# plansza_do_teleturnieju.net
KiCad netlist of a schematic drawn in EAGLE
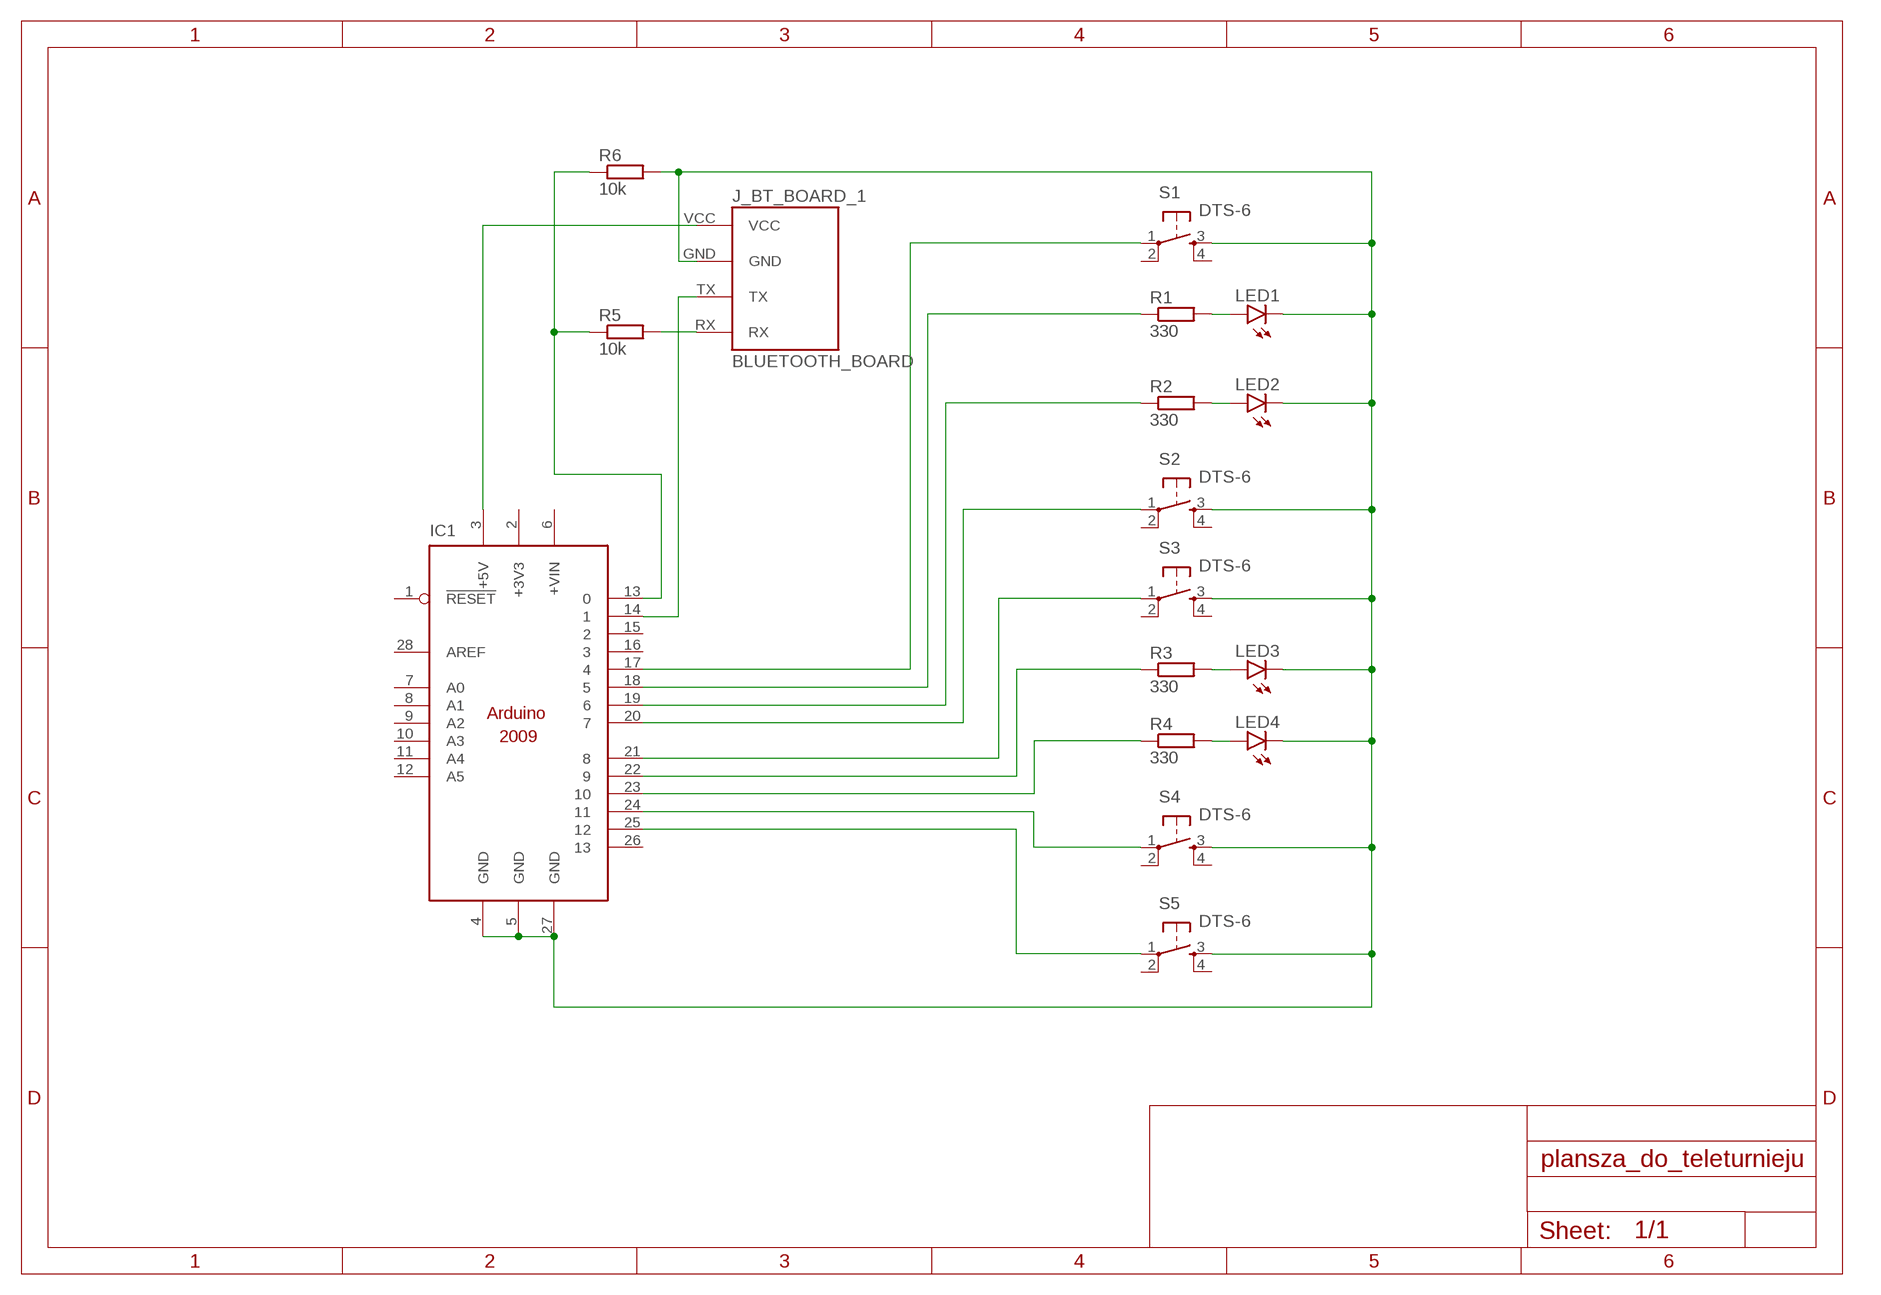
[diagram p0: schematic, sheet 1]

(export (version "E")
  (design (tool "Eeschema 10.0.6"))
  (components
    (comp (ref "IC1")
      (value "ARDUINO2009_10")
      (footprint "eagle-import:ARDUINO2009")
      (libsource (lib "eagle-import") (part "ARDUINO2009_10"))
    )
    (comp (ref "J_BT_BOARD_1")
      (value "BLUETOOTH_BOARD")
      (footprint "eagle-import:BT_BOARD_FOOTPRINT")
      (libsource (lib "eagle-import") (part "BLUETOOTH_BOARD"))
    )
    (comp (ref "LED1")
      (value "LEDLD260")
      (footprint "eagle-import:LD260")
      (libsource (lib "eagle-import") (part "LEDLD260"))
    )
    (comp (ref "LED2")
      (value "LEDLD260")
      (footprint "eagle-import:LD260")
      (libsource (lib "eagle-import") (part "LEDLD260"))
    )
    (comp (ref "LED3")
      (value "LEDLD260")
      (footprint "eagle-import:LD260")
      (libsource (lib "eagle-import") (part "LEDLD260"))
    )
    (comp (ref "LED4")
      (value "LEDLD260")
      (footprint "eagle-import:LD260")
      (libsource (lib "eagle-import") (part "LEDLD260"))
    )
    (comp (ref "R1")
      (value "330")
      (footprint "eagle-import:0204_7")
      (libsource (lib "eagle-import") (part "R-EU_0204/7"))
    )
    (comp (ref "R2")
      (value "330")
      (footprint "eagle-import:0204_7")
      (libsource (lib "eagle-import") (part "R-EU_0204/7"))
    )
    (comp (ref "R3")
      (value "330")
      (footprint "eagle-import:0204_7")
      (libsource (lib "eagle-import") (part "R-EU_0204/7"))
    )
    (comp (ref "R4")
      (value "330")
      (footprint "eagle-import:0204_7")
      (libsource (lib "eagle-import") (part "R-EU_0204/7"))
    )
    (comp (ref "R5")
      (value "10k")
      (footprint "eagle-import:0204_7")
      (libsource (lib "eagle-import") (part "R-EU_0204/7"))
    )
    (comp (ref "R6")
      (value "10k")
      (footprint "eagle-import:0204_7")
      (libsource (lib "eagle-import") (part "R-EU_0204/7"))
    )
    (comp (ref "S1")
      (value "DTS-6")
      (footprint "eagle-import:DTS-6")
      (libsource (lib "eagle-import") (part "DTS-6"))
    )
    (comp (ref "S2")
      (value "DTS-6")
      (footprint "eagle-import:DTS-6")
      (libsource (lib "eagle-import") (part "DTS-6"))
    )
    (comp (ref "S3")
      (value "DTS-6")
      (footprint "eagle-import:DTS-6")
      (libsource (lib "eagle-import") (part "DTS-6"))
    )
    (comp (ref "S4")
      (value "DTS-6")
      (footprint "eagle-import:DTS-6")
      (libsource (lib "eagle-import") (part "DTS-6"))
    )
    (comp (ref "S5")
      (value "DTS-6")
      (footprint "eagle-import:DTS-6")
      (libsource (lib "eagle-import") (part "DTS-6"))
    )
  )
  (nets
    (net (code "1") (name "/+3V3") (class "Default")
      (node (ref "IC1") (pin "2") (pinfunction "+3V3_2") (pintype "power_in"))
    )
    (net (code "2") (name "Net-(IC1-+5V)") (class "Default")
      (node (ref "IC1") (pin "3") (pinfunction "+5V_3") (pintype "power_in"))
      (node (ref "J_BT_BOARD_1") (pin "VCC") (pinfunction "VCC_VCC") (pintype "bidirectional"))
    )
    (net (code "3") (name "Net-(IC1-0)") (class "Default")
      (node (ref "IC1") (pin "13") (pinfunction "0_13") (pintype "bidirectional"))
      (node (ref "R5") (pin "1") (pinfunction "1_1") (pintype "passive"))
      (node (ref "R6") (pin "1") (pinfunction "1_1") (pintype "passive"))
    )
    (net (code "4") (name "Net-(IC1-1)") (class "Default")
      (node (ref "IC1") (pin "14") (pinfunction "1_14") (pintype "bidirectional"))
      (node (ref "J_BT_BOARD_1") (pin "TX") (pinfunction "TX_TX") (pintype "bidirectional"))
    )
    (net (code "5") (name "Net-(IC1-4)") (class "Default")
      (node (ref "IC1") (pin "17") (pinfunction "4_17") (pintype "bidirectional"))
      (node (ref "S1") (pin "1") (pinfunction "1_1") (pintype "passive"))
    )
    (net (code "6") (name "Net-(IC1-5)") (class "Default")
      (node (ref "IC1") (pin "18") (pinfunction "5_18") (pintype "bidirectional"))
      (node (ref "R1") (pin "1") (pinfunction "1_1") (pintype "passive"))
    )
    (net (code "7") (name "Net-(IC1-6)") (class "Default")
      (node (ref "IC1") (pin "19") (pinfunction "6_19") (pintype "bidirectional"))
      (node (ref "R2") (pin "1") (pinfunction "1_1") (pintype "passive"))
    )
    (net (code "8") (name "Net-(IC1-7)") (class "Default")
      (node (ref "IC1") (pin "20") (pinfunction "7_20") (pintype "bidirectional"))
      (node (ref "S2") (pin "1") (pinfunction "1_1") (pintype "passive"))
    )
    (net (code "9") (name "Net-(IC1-8)") (class "Default")
      (node (ref "IC1") (pin "21") (pinfunction "8_21") (pintype "bidirectional"))
      (node (ref "S3") (pin "1") (pinfunction "1_1") (pintype "passive"))
    )
    (net (code "10") (name "Net-(IC1-9)") (class "Default")
      (node (ref "IC1") (pin "22") (pinfunction "9_22") (pintype "bidirectional"))
      (node (ref "R3") (pin "1") (pinfunction "1_1") (pintype "passive"))
    )
    (net (code "11") (name "Net-(IC1-10)") (class "Default")
      (node (ref "IC1") (pin "23") (pinfunction "10_23") (pintype "bidirectional"))
      (node (ref "R4") (pin "1") (pinfunction "1_1") (pintype "passive"))
    )
    (net (code "12") (name "Net-(IC1-11)") (class "Default")
      (node (ref "IC1") (pin "24") (pinfunction "11_24") (pintype "bidirectional"))
      (node (ref "S4") (pin "1") (pinfunction "1_1") (pintype "passive"))
    )
    (net (code "13") (name "Net-(IC1-12)") (class "Default")
      (node (ref "IC1") (pin "25") (pinfunction "12_25") (pintype "bidirectional"))
      (node (ref "S5") (pin "1") (pinfunction "1_1") (pintype "passive"))
    )
    (net (code "14") (name "Net-(J_BT_BOARD_1-PadRX)") (class "Default")
      (node (ref "J_BT_BOARD_1") (pin "RX") (pinfunction "RX_RX") (pintype "bidirectional"))
      (node (ref "R5") (pin "2") (pinfunction "2_2") (pintype "passive"))
    )
    (net (code "15") (name "Net-(LED1-C)") (class "Default")
      (node (ref "IC1") (pin "27") (pinfunction "GND_27") (pintype "power_in"))
      (node (ref "IC1") (pin "4") (pinfunction "GND_4") (pintype "power_in"))
      (node (ref "IC1") (pin "5") (pinfunction "GND_5") (pintype "power_in"))
      (node (ref "J_BT_BOARD_1") (pin "GND") (pinfunction "GND_GND") (pintype "bidirectional"))
      (node (ref "LED1") (pin "K") (pinfunction "C_K") (pintype "passive"))
      (node (ref "LED2") (pin "K") (pinfunction "C_K") (pintype "passive"))
      (node (ref "LED3") (pin "K") (pinfunction "C_K") (pintype "passive"))
      (node (ref "LED4") (pin "K") (pinfunction "C_K") (pintype "passive"))
      (node (ref "R6") (pin "2") (pinfunction "2_2") (pintype "passive"))
      (node (ref "S1") (pin "3") (pinfunction "3_3") (pintype "passive"))
      (node (ref "S2") (pin "3") (pinfunction "3_3") (pintype "passive"))
      (node (ref "S3") (pin "3") (pinfunction "3_3") (pintype "passive"))
      (node (ref "S4") (pin "3") (pinfunction "3_3") (pintype "passive"))
      (node (ref "S5") (pin "3") (pinfunction "3_3") (pintype "passive"))
    )
    (net (code "16") (name "Net-(LED1-PadA)") (class "Default")
      (node (ref "LED1") (pin "A") (pinfunction "A_A") (pintype "passive"))
      (node (ref "R1") (pin "2") (pinfunction "2_2") (pintype "passive"))
    )
    (net (code "17") (name "Net-(LED2-PadA)") (class "Default")
      (node (ref "LED2") (pin "A") (pinfunction "A_A") (pintype "passive"))
      (node (ref "R2") (pin "2") (pinfunction "2_2") (pintype "passive"))
    )
    (net (code "18") (name "Net-(LED3-PadA)") (class "Default")
      (node (ref "LED3") (pin "A") (pinfunction "A_A") (pintype "passive"))
      (node (ref "R3") (pin "2") (pinfunction "2_2") (pintype "passive"))
    )
    (net (code "19") (name "Net-(LED4-PadA)") (class "Default")
      (node (ref "LED4") (pin "A") (pinfunction "A_A") (pintype "passive"))
      (node (ref "R4") (pin "2") (pinfunction "2_2") (pintype "passive"))
    )
    (net (code "20") (name "unconnected-(IC1-+VIN-Pad6)") (class "Default")
      (node (ref "IC1") (pin "6") (pinfunction "+VIN_6") (pintype "bidirectional"))
    )
    (net (code "21") (name "unconnected-(IC1-2-Pad15)") (class "Default")
      (node (ref "IC1") (pin "15") (pinfunction "2_15") (pintype "bidirectional"))
    )
    (net (code "22") (name "unconnected-(IC1-3-Pad16)") (class "Default")
      (node (ref "IC1") (pin "16") (pinfunction "3_16") (pintype "bidirectional"))
    )
    (net (code "23") (name "unconnected-(IC1-13-Pad26)") (class "Default")
      (node (ref "IC1") (pin "26") (pinfunction "13_26") (pintype "bidirectional"))
    )
    (net (code "24") (name "unconnected-(IC1-A0-Pad7)") (class "Default")
      (node (ref "IC1") (pin "7") (pinfunction "A0_7") (pintype "bidirectional"))
    )
    (net (code "25") (name "unconnected-(IC1-A1-Pad8)") (class "Default")
      (node (ref "IC1") (pin "8") (pinfunction "A1_8") (pintype "bidirectional"))
    )
    (net (code "26") (name "unconnected-(IC1-A2-Pad9)") (class "Default")
      (node (ref "IC1") (pin "9") (pinfunction "A2_9") (pintype "bidirectional"))
    )
    (net (code "27") (name "unconnected-(IC1-A3-Pad10)") (class "Default")
      (node (ref "IC1") (pin "10") (pinfunction "A3_10") (pintype "bidirectional"))
    )
    (net (code "28") (name "unconnected-(IC1-A4-Pad11)") (class "Default")
      (node (ref "IC1") (pin "11") (pinfunction "A4_11") (pintype "bidirectional"))
    )
    (net (code "29") (name "unconnected-(IC1-A5-Pad12)") (class "Default")
      (node (ref "IC1") (pin "12") (pinfunction "A5_12") (pintype "bidirectional"))
    )
    (net (code "30") (name "unconnected-(IC1-AREF-Pad28)") (class "Default")
      (node (ref "IC1") (pin "28") (pinfunction "AREF_28") (pintype "bidirectional"))
    )
    (net (code "31") (name "unconnected-(IC1-~{RESET}-Pad1)") (class "Default")
      (node (ref "IC1") (pin "1") (pinfunction "~{RESET}_1") (pintype "bidirectional"))
    )
    (net (code "32") (name "unconnected-(S1-Pad2)") (class "Default")
      (node (ref "S1") (pin "2") (pinfunction "2_2") (pintype "passive"))
    )
    (net (code "33") (name "unconnected-(S1-Pad4)") (class "Default")
      (node (ref "S1") (pin "4") (pinfunction "4_4") (pintype "passive"))
    )
    (net (code "34") (name "unconnected-(S2-Pad2)") (class "Default")
      (node (ref "S2") (pin "2") (pinfunction "2_2") (pintype "passive"))
    )
    (net (code "35") (name "unconnected-(S2-Pad4)") (class "Default")
      (node (ref "S2") (pin "4") (pinfunction "4_4") (pintype "passive"))
    )
    (net (code "36") (name "unconnected-(S3-Pad2)") (class "Default")
      (node (ref "S3") (pin "2") (pinfunction "2_2") (pintype "passive"))
    )
    (net (code "37") (name "unconnected-(S3-Pad4)") (class "Default")
      (node (ref "S3") (pin "4") (pinfunction "4_4") (pintype "passive"))
    )
    (net (code "38") (name "unconnected-(S4-Pad2)") (class "Default")
      (node (ref "S4") (pin "2") (pinfunction "2_2") (pintype "passive"))
    )
    (net (code "39") (name "unconnected-(S4-Pad4)") (class "Default")
      (node (ref "S4") (pin "4") (pinfunction "4_4") (pintype "passive"))
    )
    (net (code "40") (name "unconnected-(S5-Pad2)") (class "Default")
      (node (ref "S5") (pin "2") (pinfunction "2_2") (pintype "passive"))
    )
    (net (code "41") (name "unconnected-(S5-Pad4)") (class "Default")
      (node (ref "S5") (pin "4") (pinfunction "4_4") (pintype "passive"))
    )
  )
)
